# Chassis.net
KiCad netlist of a schematic drawn in Altium Designer
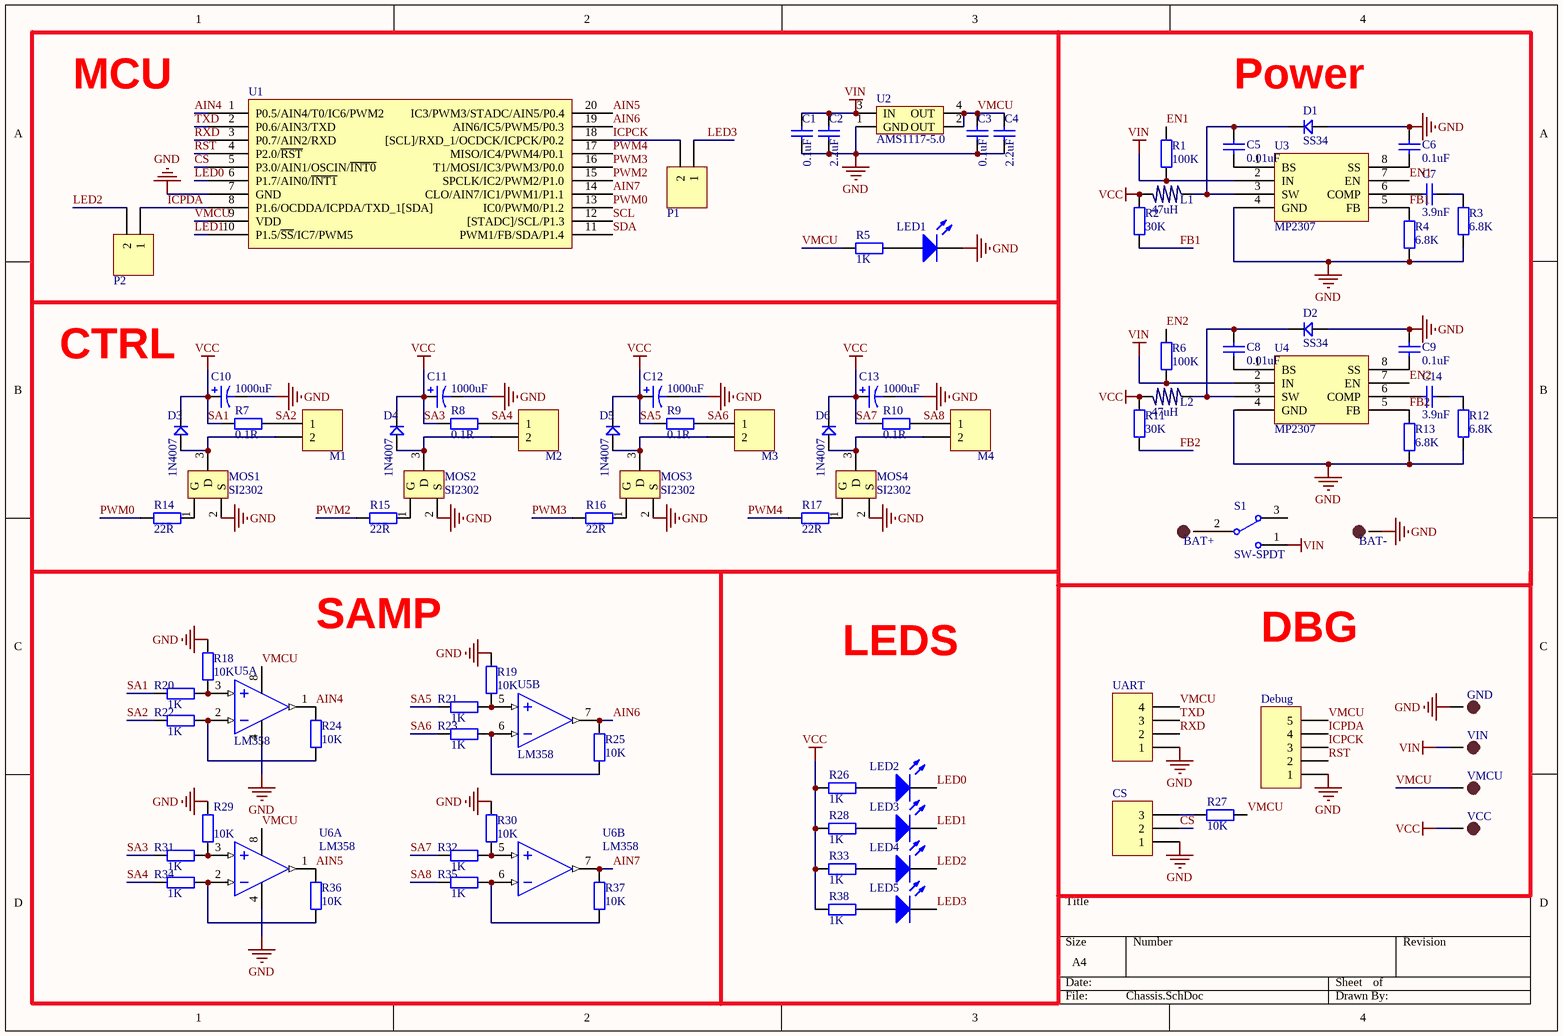
[diagram p0: Chassis.SchDoc]

(export (version "E")
  (design (tool "Eeschema 10.0.6"))
  (components
    (comp (ref "BAT+")
      (value "SPK+")
      (footprint "TP-1.5")
      (description "测试点")
      (libsource (lib "STM32F429_F746") (part "TEST-POINT"))
    )
    (comp (ref "BAT-")
      (value "SPK+")
      (footprint "TP-1.5")
      (description "测试点")
      (libsource (lib "STM32F429_F746") (part "TEST-POINT"))
    )
    (comp (ref "C1")
      (value "0.1uF")
      (footprint "0603P")
      (description "Capacitor")
      (fields (field (name "Comment") "Cap") (field (name "PUBLISHER") "Altium Limited"))
      (libsource (lib "Miscellaneous Devices") (part "Cap"))
    )
    (comp (ref "C2")
      (value "2.2uF")
      (footprint "0603P")
      (description "Capacitor")
      (fields (field (name "Comment") "Cap") (field (name "PUBLISHER") "Altium Limited"))
      (libsource (lib "Miscellaneous Devices") (part "Cap"))
    )
    (comp (ref "C3")
      (value "0.1uF")
      (footprint "0603P")
      (description "Capacitor")
      (fields (field (name "Comment") "Cap") (field (name "PUBLISHER") "Altium Limited"))
      (libsource (lib "Miscellaneous Devices") (part "Cap"))
    )
    (comp (ref "C4")
      (value "2.2uF")
      (footprint "0603P")
      (description "Capacitor")
      (fields (field (name "Comment") "Cap") (field (name "PUBLISHER") "Altium Limited"))
      (libsource (lib "Miscellaneous Devices") (part "Cap"))
    )
    (comp (ref "C5")
      (value "0.01uF")
      (footprint "0603P")
      (description "Capacitor")
      (fields (field (name "Comment") "Cap") (field (name "PUBLISHER") "Altium Limited"))
      (libsource (lib "Miscellaneous Devices") (part "Cap"))
    )
    (comp (ref "C6")
      (value "0.1uF")
      (footprint "0603P")
      (description "Capacitor")
      (fields (field (name "Comment") "Cap") (field (name "PUBLISHER") "Altium Limited"))
      (libsource (lib "Miscellaneous Devices") (part "Cap"))
    )
    (comp (ref "C7")
      (value "3.9nF")
      (footprint "0603P")
      (description "Capacitor")
      (fields (field (name "Comment") "Cap") (field (name "PUBLISHER") "Altium Limited"))
      (libsource (lib "Miscellaneous Devices") (part "Cap"))
    )
    (comp (ref "C8")
      (value "0.01uF")
      (footprint "0603P")
      (description "Capacitor")
      (fields (field (name "Comment") "Cap") (field (name "PUBLISHER") "Altium Limited"))
      (libsource (lib "Miscellaneous Devices") (part "Cap"))
    )
    (comp (ref "C9")
      (value "0.1uF")
      (footprint "0603P")
      (description "Capacitor")
      (fields (field (name "Comment") "Cap") (field (name "PUBLISHER") "Altium Limited"))
      (libsource (lib "Miscellaneous Devices") (part "Cap"))
    )
    (comp (ref "C10")
      (value "1000uF")
      (footprint "C-RB-5.0/13")
      (description "Polarized Capacitor (Radial)")
      (fields (field (name "Comment") "Cap Pol1") (field (name "PUBLISHER") "Altium Limited"))
      (libsource (lib "Miscellaneous Devices") (part "Cap Pol1"))
    )
    (comp (ref "C11")
      (value "1000uF")
      (footprint "C-RB-5.0/13")
      (description "Polarized Capacitor (Radial)")
      (fields (field (name "Comment") "Cap Pol1") (field (name "PUBLISHER") "Altium Limited"))
      (libsource (lib "Miscellaneous Devices") (part "Cap Pol1"))
    )
    (comp (ref "C12")
      (value "1000uF")
      (footprint "C-RB-5.0/13")
      (description "Polarized Capacitor (Radial)")
      (fields (field (name "Comment") "Cap Pol1") (field (name "PUBLISHER") "Altium Limited"))
      (libsource (lib "Miscellaneous Devices") (part "Cap Pol1"))
    )
    (comp (ref "C13")
      (value "1000uF")
      (footprint "C-RB-5.0/13")
      (description "Polarized Capacitor (Radial)")
      (fields (field (name "Comment") "Cap Pol1") (field (name "PUBLISHER") "Altium Limited"))
      (libsource (lib "Miscellaneous Devices") (part "Cap Pol1"))
    )
    (comp (ref "C14")
      (value "3.9nF")
      (footprint "0603P")
      (description "Capacitor")
      (fields (field (name "Comment") "Cap") (field (name "PUBLISHER") "Altium Limited"))
      (libsource (lib "Miscellaneous Devices") (part "Cap"))
    )
    (comp (ref "CS")
      (value "Header 3")
      (footprint "HDR1X3")
      (description "Header, 3-Pin")
      (fields (field (name "PUBLISHER") "Altium Limited"))
      (libsource (lib "Miscellaneous Connectors") (part "Header 3"))
    )
    (comp (ref "D1") (value "SS34") (footprint "SOD-123") (libsource (lib "STM32F429_F746") (part "D")))
    (comp (ref "D2") (value "SS34") (footprint "SOD-123") (libsource (lib "STM32F429_F746") (part "D")))
    (comp (ref "D3") (value "1N4007") (footprint "SOD-123") (libsource (lib "STM32F429_F746") (part "D")))
    (comp (ref "D4") (value "1N4007") (footprint "SOD-123") (libsource (lib "STM32F429_F746") (part "D")))
    (comp (ref "D5") (value "1N4007") (footprint "SOD-123") (libsource (lib "STM32F429_F746") (part "D")))
    (comp (ref "D6") (value "1N4007") (footprint "SOD-123") (libsource (lib "STM32F429_F746") (part "D")))
    (comp (ref "Debug")
      (value "Header 5")
      (footprint "HDR1X5")
      (description "Header, 5-Pin")
      (fields (field (name "PUBLISHER") "Altium Limited"))
      (libsource (lib "Miscellaneous Connectors") (part "Header 5"))
    )
    (comp (ref "GND")
      (value "SPK+")
      (footprint "TP-1.5")
      (description "测试点")
      (libsource (lib "STM32F429_F746") (part "TEST-POINT"))
    )
    (comp (ref "L1") (value "47uH") (footprint "0603P") (libsource (lib "STM32F429_F746") (part "L")))
    (comp (ref "L2") (value "47uH") (footprint "0603P") (libsource (lib "STM32F429_F746") (part "L")))
    (comp (ref "LED1")
      (value "LED1")
      (footprint "LED-1206")
      (description "Typical RED, GREEN, YELLOW, AMBER GaAs LED")
      (fields (field (name "PUBLISHER") "Altium Limited"))
      (libsource (lib "STM32F429_F746") (part "LED2"))
    )
    (comp (ref "LED2")
      (value "LED1")
      (footprint "LED-1206")
      (description "Typical RED, GREEN, YELLOW, AMBER GaAs LED")
      (fields (field (name "PUBLISHER") "Altium Limited"))
      (libsource (lib "STM32F429_F746") (part "LED2"))
    )
    (comp (ref "LED3")
      (value "LED1")
      (footprint "LED-1206")
      (description "Typical RED, GREEN, YELLOW, AMBER GaAs LED")
      (fields (field (name "PUBLISHER") "Altium Limited"))
      (libsource (lib "STM32F429_F746") (part "LED2"))
    )
    (comp (ref "LED4")
      (value "LED1")
      (footprint "LED-1206")
      (description "Typical RED, GREEN, YELLOW, AMBER GaAs LED")
      (fields (field (name "PUBLISHER") "Altium Limited"))
      (libsource (lib "STM32F429_F746") (part "LED2"))
    )
    (comp (ref "LED5")
      (value "LED1")
      (footprint "LED-1206")
      (description "Typical RED, GREEN, YELLOW, AMBER GaAs LED")
      (fields (field (name "PUBLISHER") "Altium Limited"))
      (libsource (lib "STM32F429_F746") (part "LED2"))
    )
    (comp (ref "M1")
      (value "Header 2")
      (footprint "HDR1X2")
      (description "Header, 2-Pin")
      (fields (field (name "PUBLISHER") "Altium Limited"))
      (libsource (lib "") (part "Header 2_1"))
    )
    (comp (ref "M2")
      (value "Header 2")
      (footprint "HDR1X2")
      (description "Header, 2-Pin")
      (fields (field (name "PUBLISHER") "Altium Limited"))
      (libsource (lib "") (part "Header 2_1"))
    )
    (comp (ref "M3")
      (value "Header 2")
      (footprint "HDR1X2")
      (description "Header, 2-Pin")
      (fields (field (name "PUBLISHER") "Altium Limited"))
      (libsource (lib "") (part "Header 2_1"))
    )
    (comp (ref "M4")
      (value "Header 2")
      (footprint "HDR1X2")
      (description "Header, 2-Pin")
      (fields (field (name "PUBLISHER") "Altium Limited"))
      (libsource (lib "") (part "Header 2_1"))
    )
    (comp (ref "MOS1")
      (value "SI2302")
      (footprint "SO-G3/C2.5")
      (description "IRLML6401/SI2301")
      (libsource (lib "STM32F429_CORE") (part "MOS-P"))
    )
    (comp (ref "MOS2")
      (value "SI2302")
      (footprint "SO-G3/C2.5")
      (description "IRLML6401/SI2301")
      (libsource (lib "STM32F429_CORE") (part "MOS-P"))
    )
    (comp (ref "MOS3")
      (value "SI2302")
      (footprint "SO-G3/C2.5")
      (description "IRLML6401/SI2301")
      (libsource (lib "STM32F429_CORE") (part "MOS-P"))
    )
    (comp (ref "MOS4")
      (value "SI2302")
      (footprint "SO-G3/C2.5")
      (description "IRLML6401/SI2301")
      (libsource (lib "STM32F429_CORE") (part "MOS-P"))
    )
    (comp (ref "P1")
      (value "Header 2")
      (footprint "HDR1X2")
      (description "Header, 2-Pin")
      (fields (field (name "PUBLISHER") "Altium Limited"))
      (libsource (lib "Miscellaneous Connectors") (part "Header 2"))
    )
    (comp (ref "P2")
      (value "Header 2")
      (footprint "HDR1X2")
      (description "Header, 2-Pin")
      (fields (field (name "PUBLISHER") "Altium Limited"))
      (libsource (lib "Miscellaneous Connectors") (part "Header 2"))
    )
    (comp (ref "R1")
      (value "100K")
      (footprint "0603P")
      (description "Resistor")
      (fields (field (name "Comment") "Res2") (field (name "PUBLISHER") "Altium Limited"))
      (libsource (lib "") (part "Res2_1"))
    )
    (comp (ref "R2")
      (value "30K")
      (footprint "0603P")
      (description "Resistor")
      (fields (field (name "Comment") "Res2") (field (name "PUBLISHER") "Altium Limited"))
      (libsource (lib "") (part "Res2_1"))
    )
    (comp (ref "R3")
      (value "6.8K")
      (footprint "0603P")
      (description "Resistor")
      (fields (field (name "Comment") "Res2") (field (name "PUBLISHER") "Altium Limited"))
      (libsource (lib "") (part "Res2_1"))
    )
    (comp (ref "R4")
      (value "6.8K")
      (footprint "0603P")
      (description "Resistor")
      (fields (field (name "Comment") "Res2") (field (name "PUBLISHER") "Altium Limited"))
      (libsource (lib "") (part "Res2_1"))
    )
    (comp (ref "R5")
      (value "1K")
      (footprint "0603P")
      (description "Resistor")
      (fields (field (name "Comment") "Res2") (field (name "PUBLISHER") "Altium Limited"))
      (libsource (lib "Miscellaneous Devices") (part "Res2"))
    )
    (comp (ref "R6")
      (value "100K")
      (footprint "0603P")
      (description "Resistor")
      (fields (field (name "Comment") "Res2") (field (name "PUBLISHER") "Altium Limited"))
      (libsource (lib "") (part "Res2_1"))
    )
    (comp (ref "R7")
      (value "0.1R")
      (footprint "2512")
      (description "Resistor")
      (fields (field (name "Comment") "Res2") (field (name "PUBLISHER") "Altium Limited"))
      (libsource (lib "Miscellaneous Devices") (part "Res2"))
    )
    (comp (ref "R8")
      (value "0.1R")
      (footprint "2512")
      (description "Resistor")
      (fields (field (name "Comment") "Res2") (field (name "PUBLISHER") "Altium Limited"))
      (libsource (lib "Miscellaneous Devices") (part "Res2"))
    )
    (comp (ref "R9")
      (value "0.1R")
      (footprint "2512")
      (description "Resistor")
      (fields (field (name "Comment") "Res2") (field (name "PUBLISHER") "Altium Limited"))
      (libsource (lib "Miscellaneous Devices") (part "Res2"))
    )
    (comp (ref "R10")
      (value "0.1R")
      (footprint "2512")
      (description "Resistor")
      (fields (field (name "Comment") "Res2") (field (name "PUBLISHER") "Altium Limited"))
      (libsource (lib "Miscellaneous Devices") (part "Res2"))
    )
    (comp (ref "R11")
      (value "30K")
      (footprint "0603p")
      (description "Resistor")
      (fields (field (name "Comment") "Res2") (field (name "PUBLISHER") "Altium Limited"))
      (libsource (lib "") (part "Res2_1"))
    )
    (comp (ref "R12")
      (value "6.8K")
      (footprint "0603p")
      (description "Resistor")
      (fields (field (name "Comment") "Res2") (field (name "PUBLISHER") "Altium Limited"))
      (libsource (lib "") (part "Res2_1"))
    )
    (comp (ref "R13")
      (value "6.8K")
      (footprint "0603p")
      (description "Resistor")
      (fields (field (name "Comment") "Res2") (field (name "PUBLISHER") "Altium Limited"))
      (libsource (lib "") (part "Res2_1"))
    )
    (comp (ref "R14")
      (value "22R")
      (footprint "0603p")
      (description "Resistor")
      (fields (field (name "Comment") "Res2") (field (name "PUBLISHER") "Altium Limited"))
      (libsource (lib "Miscellaneous Devices") (part "Res2"))
    )
    (comp (ref "R15")
      (value "22R")
      (footprint "0603p")
      (description "Resistor")
      (fields (field (name "Comment") "Res2") (field (name "PUBLISHER") "Altium Limited"))
      (libsource (lib "Miscellaneous Devices") (part "Res2"))
    )
    (comp (ref "R16")
      (value "22R")
      (footprint "0603p")
      (description "Resistor")
      (fields (field (name "Comment") "Res2") (field (name "PUBLISHER") "Altium Limited"))
      (libsource (lib "Miscellaneous Devices") (part "Res2"))
    )
    (comp (ref "R17")
      (value "22R")
      (footprint "0603p")
      (description "Resistor")
      (fields (field (name "Comment") "Res2") (field (name "PUBLISHER") "Altium Limited"))
      (libsource (lib "Miscellaneous Devices") (part "Res2"))
    )
    (comp (ref "R18")
      (value "10K")
      (footprint "0603p")
      (description "Resistor")
      (fields (field (name "Comment") "Res2") (field (name "PUBLISHER") "Altium Limited"))
      (libsource (lib "") (part "Res2_1"))
    )
    (comp (ref "R19")
      (value "10K")
      (footprint "0603p")
      (description "Resistor")
      (fields (field (name "Comment") "Res2") (field (name "PUBLISHER") "Altium Limited"))
      (libsource (lib "") (part "Res2_1"))
    )
    (comp (ref "R20")
      (value "1K")
      (footprint "0603p")
      (description "Resistor")
      (fields (field (name "Comment") "Res2") (field (name "PUBLISHER") "Altium Limited"))
      (libsource (lib "Miscellaneous Devices") (part "Res2"))
    )
    (comp (ref "R21")
      (value "1K")
      (footprint "0603p")
      (description "Resistor")
      (fields (field (name "Comment") "Res2") (field (name "PUBLISHER") "Altium Limited"))
      (libsource (lib "Miscellaneous Devices") (part "Res2"))
    )
    (comp (ref "R22")
      (value "1K")
      (footprint "0603p")
      (description "Resistor")
      (fields (field (name "Comment") "Res2") (field (name "PUBLISHER") "Altium Limited"))
      (libsource (lib "Miscellaneous Devices") (part "Res2"))
    )
    (comp (ref "R23")
      (value "1K")
      (footprint "0603p")
      (description "Resistor")
      (fields (field (name "Comment") "Res2") (field (name "PUBLISHER") "Altium Limited"))
      (libsource (lib "Miscellaneous Devices") (part "Res2"))
    )
    (comp (ref "R24")
      (value "10K")
      (footprint "0603p")
      (description "Resistor")
      (fields (field (name "Comment") "Res2") (field (name "PUBLISHER") "Altium Limited"))
      (libsource (lib "") (part "Res2_1"))
    )
    (comp (ref "R25")
      (value "10K")
      (footprint "0603p")
      (description "Resistor")
      (fields (field (name "Comment") "Res2") (field (name "PUBLISHER") "Altium Limited"))
      (libsource (lib "") (part "Res2_1"))
    )
    (comp (ref "R26")
      (value "1K")
      (footprint "0603p")
      (description "Resistor")
      (fields (field (name "Comment") "Res2") (field (name "PUBLISHER") "Altium Limited"))
      (libsource (lib "Miscellaneous Devices") (part "Res2"))
    )
    (comp (ref "R27")
      (value "10K")
      (footprint "0603p")
      (description "Resistor")
      (fields (field (name "Comment") "Res2") (field (name "PUBLISHER") "Altium Limited"))
      (libsource (lib "Miscellaneous Devices") (part "Res2"))
    )
    (comp (ref "R28")
      (value "1K")
      (footprint "0603p")
      (description "Resistor")
      (fields (field (name "Comment") "Res2") (field (name "PUBLISHER") "Altium Limited"))
      (libsource (lib "Miscellaneous Devices") (part "Res2"))
    )
    (comp (ref "R29")
      (value "10K")
      (footprint "0603p")
      (description "Resistor")
      (fields (field (name "Comment") "Res2") (field (name "PUBLISHER") "Altium Limited"))
      (libsource (lib "") (part "Res2_1"))
    )
    (comp (ref "R30")
      (value "10K")
      (footprint "0603p")
      (description "Resistor")
      (fields (field (name "Comment") "Res2") (field (name "PUBLISHER") "Altium Limited"))
      (libsource (lib "") (part "Res2_1"))
    )
    (comp (ref "R31")
      (value "1K")
      (footprint "0603p")
      (description "Resistor")
      (fields (field (name "Comment") "Res2") (field (name "PUBLISHER") "Altium Limited"))
      (libsource (lib "Miscellaneous Devices") (part "Res2"))
    )
    (comp (ref "R32")
      (value "1K")
      (footprint "0603p")
      (description "Resistor")
      (fields (field (name "Comment") "Res2") (field (name "PUBLISHER") "Altium Limited"))
      (libsource (lib "Miscellaneous Devices") (part "Res2"))
    )
    (comp (ref "R33")
      (value "1K")
      (footprint "0603p")
      (description "Resistor")
      (fields (field (name "Comment") "Res2") (field (name "PUBLISHER") "Altium Limited"))
      (libsource (lib "Miscellaneous Devices") (part "Res2"))
    )
    (comp (ref "R34")
      (value "1K")
      (footprint "0603p")
      (description "Resistor")
      (fields (field (name "Comment") "Res2") (field (name "PUBLISHER") "Altium Limited"))
      (libsource (lib "Miscellaneous Devices") (part "Res2"))
    )
    (comp (ref "R35")
      (value "1K")
      (footprint "0603p")
      (description "Resistor")
      (fields (field (name "Comment") "Res2") (field (name "PUBLISHER") "Altium Limited"))
      (libsource (lib "Miscellaneous Devices") (part "Res2"))
    )
    (comp (ref "R36")
      (value "10K")
      (footprint "0603p")
      (description "Resistor")
      (fields (field (name "Comment") "Res2") (field (name "PUBLISHER") "Altium Limited"))
      (libsource (lib "") (part "Res2_1"))
    )
    (comp (ref "R37")
      (value "10K")
      (footprint "0603p")
      (description "Resistor")
      (fields (field (name "Comment") "Res2") (field (name "PUBLISHER") "Altium Limited"))
      (libsource (lib "") (part "Res2_1"))
    )
    (comp (ref "R38")
      (value "1K")
      (footprint "0603p")
      (description "Resistor")
      (fields (field (name "Comment") "Res2") (field (name "PUBLISHER") "Altium Limited"))
      (libsource (lib "Miscellaneous Devices") (part "Res2"))
    )
    (comp (ref "S1")
      (value "SW-SPDT")
      (footprint "SWITCH_A3")
      (description "开关")
      (fields (field (name "PUBLISHER") "Altium Limited"))
      (libsource (lib "fszhang") (part "SW-SPDT"))
    )
    (comp (ref "U1")
      (value "N76E003")
      (footprint "SSOP-20_208mil")
      (libsource (lib "nvton") (part "N76E003"))
    )
    (comp (ref "U2")
      (value "AMS1117-5.0")
      (footprint "AMS1117")
      (libsource (lib "STM32F429_F746") (part "AMS1117"))
    )
    (comp (ref "U3") (value "MP2307") (footprint "SOP-8") (libsource (lib "STM32F429_F746") (part "MP2307")))
    (comp (ref "U4") (value "MP2307") (footprint "SOP-8") (libsource (lib "STM32F429_F746") (part "MP2307")))
    (comp (ref "U5")
      (value "LM358")
      (footprint "SOIC-8")
      (description "双运放")
      (libsource (lib "fszhang") (part "LM358"))
    )
    (comp (ref "U6")
      (value "LM358")
      (footprint "SOIC-8")
      (description "双运放")
      (libsource (lib "fszhang") (part "LM358"))
    )
    (comp (ref "UART")
      (value "Header 4")
      (footprint "HDR1X4")
      (description "Header, 4-Pin")
      (fields (field (name "PUBLISHER") "Altium Limited"))
      (libsource (lib "Miscellaneous Connectors") (part "Header 4"))
    )
    (comp (ref "VCC")
      (value "SPK+")
      (footprint "TP-1.5")
      (description "测试点")
      (libsource (lib "STM32F429_F746") (part "TEST-POINT"))
    )
    (comp (ref "VIN")
      (value "SPK+")
      (footprint "TP-1.5")
      (description "测试点")
      (libsource (lib "STM32F429_F746") (part "TEST-POINT"))
    )
    (comp (ref "VMCU")
      (value "SPK+")
      (footprint "TP-1.5")
      (description "测试点")
      (libsource (lib "STM32F429_F746") (part "TEST-POINT"))
    )
  )
  (nets
    (net (code "1") (name "/AIN4") (class "Default")
      (node (ref "R24") (pin "2") (pinfunction "2_2") (pintype "passive"))
      (node (ref "U1") (pin "1") (pinfunction "P0.5/AIN4/T0/IC6/PWM2_1") (pintype "passive"))
      (node (ref "U5") (pin "1") (pinfunction "OUT_1") (pintype "output"))
    )
    (net (code "2") (name "/AIN5") (class "Default")
      (node (ref "R36") (pin "2") (pinfunction "2_2") (pintype "passive"))
      (node (ref "U1") (pin "20") (pinfunction "IC3/PWM3/STADC/AIN5/P0.4_20") (pintype "passive"))
      (node (ref "U6") (pin "1") (pinfunction "OUT_1") (pintype "output"))
    )
    (net (code "3") (name "/AIN6") (class "Default")
      (node (ref "R25") (pin "2") (pinfunction "2_2") (pintype "passive"))
      (node (ref "U1") (pin "19") (pinfunction "AIN6/IC5/PWM5/P0.3_19") (pintype "passive"))
      (node (ref "U5") (pin "7") (pinfunction "OUT_7") (pintype "output"))
    )
    (net (code "4") (name "/AIN7") (class "Default")
      (node (ref "R37") (pin "2") (pinfunction "2_2") (pintype "passive"))
      (node (ref "U1") (pin "14") (pinfunction "CLO/AIN7/IC1/PWM1/P1.1_14") (pintype "passive"))
      (node (ref "U6") (pin "7") (pinfunction "OUT_7") (pintype "output"))
    )
    (net (code "5") (name "/CS") (class "Default")
      (node (ref "CS") (pin "2") (pinfunction "2_2") (pintype "passive"))
      (node (ref "U1") (pin "5") (pinfunction "P3.0/AIN1/OSCIN/~{INT0}_5") (pintype "passive"))
    )
    (net (code "6") (name "/EN1") (class "Default")
      (node (ref "R1") (pin "2") (pinfunction "2_2") (pintype "passive"))
      (node (ref "U3") (pin "7") (pinfunction "EN_7") (pintype "passive"))
    )
    (net (code "7") (name "/EN2") (class "Default")
      (node (ref "R6") (pin "2") (pinfunction "2_2") (pintype "passive"))
      (node (ref "U4") (pin "7") (pinfunction "EN_7") (pintype "passive"))
    )
    (net (code "8") (name "/FB1") (class "Default")
      (node (ref "R2") (pin "1") (pinfunction "1_1") (pintype "passive"))
      (node (ref "R4") (pin "2") (pinfunction "2_2") (pintype "passive"))
      (node (ref "U3") (pin "5") (pinfunction "FB_5") (pintype "passive"))
    )
    (net (code "9") (name "/FB2") (class "Default")
      (node (ref "R11") (pin "1") (pinfunction "1_1") (pintype "passive"))
      (node (ref "R13") (pin "2") (pinfunction "2_2") (pintype "passive"))
      (node (ref "U4") (pin "5") (pinfunction "FB_5") (pintype "passive"))
    )
    (net (code "10") (name "/ICPCK") (class "Default")
      (node (ref "Debug") (pin "3") (pinfunction "3_3") (pintype "passive"))
      (node (ref "P1") (pin "2") (pinfunction "2_2") (pintype "passive"))
      (node (ref "U1") (pin "18") (pinfunction "[SCL]/RXD_1/OCDCK/ICPCK/P0.2_18") (pintype "passive"))
    )
    (net (code "11") (name "/ICPDA") (class "Default")
      (node (ref "Debug") (pin "4") (pinfunction "4_4") (pintype "passive"))
      (node (ref "P2") (pin "1") (pinfunction "1_1") (pintype "passive"))
      (node (ref "U1") (pin "8") (pinfunction "P1.6/OCDDA/ICPDA/TXD_1[SDA]_8") (pintype "passive"))
    )
    (net (code "12") (name "/LED0") (class "Default")
      (node (ref "LED2") (pin "2") (pinfunction "K_2") (pintype "passive"))
      (node (ref "U1") (pin "6") (pinfunction "P1.7/AIN0/~{INT1}_6") (pintype "passive"))
    )
    (net (code "13") (name "/LED1") (class "Default")
      (node (ref "LED3") (pin "2") (pinfunction "K_2") (pintype "passive"))
      (node (ref "U1") (pin "10") (pinfunction "P1.5/~{SS}/IC7/PWM5_10") (pintype "passive"))
    )
    (net (code "14") (name "/LED2") (class "Default")
      (node (ref "LED4") (pin "2") (pinfunction "K_2") (pintype "passive"))
      (node (ref "P2") (pin "2") (pinfunction "2_2") (pintype "passive"))
    )
    (net (code "15") (name "/LED3") (class "Default")
      (node (ref "LED5") (pin "2") (pinfunction "K_2") (pintype "passive"))
      (node (ref "P1") (pin "1") (pinfunction "1_1") (pintype "passive"))
    )
    (net (code "16") (name "/PWM0") (class "Default")
      (node (ref "R14") (pin "1") (pinfunction "1_1") (pintype "passive"))
      (node (ref "U1") (pin "13") (pinfunction "IC0/PWM0/P1.2_13") (pintype "passive"))
    )
    (net (code "17") (name "/PWM2") (class "Default")
      (node (ref "R15") (pin "1") (pinfunction "1_1") (pintype "passive"))
      (node (ref "U1") (pin "15") (pinfunction "SPCLK/IC2/PWM2/P1.0_15") (pintype "passive"))
    )
    (net (code "18") (name "/PWM3") (class "Default")
      (node (ref "R16") (pin "1") (pinfunction "1_1") (pintype "passive"))
      (node (ref "U1") (pin "16") (pinfunction "T1/MOSI/IC3/PWM3/P0.0_16") (pintype "passive"))
    )
    (net (code "19") (name "/PWM4") (class "Default")
      (node (ref "R17") (pin "1") (pinfunction "1_1") (pintype "passive"))
      (node (ref "U1") (pin "17") (pinfunction "MISO/IC4/PWM4/P0.1_17") (pintype "passive"))
    )
    (net (code "20") (name "/RST") (class "Default")
      (node (ref "Debug") (pin "2") (pinfunction "2_2") (pintype "passive"))
      (node (ref "U1") (pin "4") (pinfunction "P2.0/~{RST}_4") (pintype "passive"))
    )
    (net (code "21") (name "/RXD") (class "Default")
      (node (ref "U1") (pin "3") (pinfunction "P0.7/AIN2/RXD_3") (pintype "passive"))
      (node (ref "UART") (pin "2") (pinfunction "2_2") (pintype "passive"))
    )
    (net (code "22") (name "/SA2") (class "Default")
      (node (ref "M1") (pin "1") (pinfunction "1_1") (pintype "passive"))
      (node (ref "R22") (pin "1") (pinfunction "1_1") (pintype "passive"))
      (node (ref "R7") (pin "2") (pinfunction "2_2") (pintype "passive"))
    )
    (net (code "23") (name "/SA4") (class "Default")
      (node (ref "M2") (pin "1") (pinfunction "1_1") (pintype "passive"))
      (node (ref "R34") (pin "1") (pinfunction "1_1") (pintype "passive"))
      (node (ref "R8") (pin "2") (pinfunction "2_2") (pintype "passive"))
    )
    (net (code "24") (name "/SA6") (class "Default")
      (node (ref "M3") (pin "1") (pinfunction "1_1") (pintype "passive"))
      (node (ref "R23") (pin "1") (pinfunction "1_1") (pintype "passive"))
      (node (ref "R9") (pin "2") (pinfunction "2_2") (pintype "passive"))
    )
    (net (code "25") (name "/SA8") (class "Default")
      (node (ref "M4") (pin "1") (pinfunction "1_1") (pintype "passive"))
      (node (ref "R10") (pin "2") (pinfunction "2_2") (pintype "passive"))
      (node (ref "R35") (pin "1") (pinfunction "1_1") (pintype "passive"))
    )
    (net (code "26") (name "/SCL") (class "Default")
      (node (ref "U1") (pin "12") (pinfunction "[STADC]/SCL/P1.3_12") (pintype "passive"))
    )
    (net (code "27") (name "/SDA") (class "Default")
      (node (ref "U1") (pin "11") (pinfunction "PWM1/FB/SDA/P1.4_11") (pintype "passive"))
    )
    (net (code "28") (name "/TXD") (class "Default")
      (node (ref "U1") (pin "2") (pinfunction "P0.6/AIN3/TXD_2") (pintype "passive"))
      (node (ref "UART") (pin "3") (pinfunction "3_3") (pintype "passive"))
    )
    (net (code "29") (name "/VMCU") (class "Default")
      (node (ref "C3") (pin "2") (pinfunction "2_2") (pintype "passive"))
      (node (ref "C4") (pin "2") (pinfunction "2_2") (pintype "passive"))
      (node (ref "Debug") (pin "5") (pinfunction "5_5") (pintype "passive"))
      (node (ref "R27") (pin "2") (pinfunction "2_2") (pintype "passive"))
      (node (ref "R5") (pin "1") (pinfunction "1_1") (pintype "passive"))
      (node (ref "U1") (pin "9") (pinfunction "VDD_9") (pintype "passive"))
      (node (ref "U2") (pin "2") (pinfunction "OUT_2") (pintype "passive"))
      (node (ref "U2") (pin "4") (pinfunction "OUT_4") (pintype "passive"))
      (node (ref "U5") (pin "8") (pinfunction "V+_8") (pintype "passive"))
      (node (ref "U6") (pin "8") (pinfunction "V+_8") (pintype "passive"))
      (node (ref "UART") (pin "4") (pinfunction "4_4") (pintype "passive"))
      (node (ref "VMCU") (pin "1") (pinfunction "1_1") (pintype "passive"))
    )
    (net (code "30") (name "GND") (class "Default")
      (node (ref "BAT-") (pin "1") (pinfunction "1_1") (pintype "passive"))
      (node (ref "C1") (pin "1") (pinfunction "1_1") (pintype "passive"))
      (node (ref "C10") (pin "2") (pinfunction "2_2") (pintype "passive"))
      (node (ref "C11") (pin "2") (pinfunction "2_2") (pintype "passive"))
      (node (ref "C12") (pin "2") (pinfunction "2_2") (pintype "passive"))
      (node (ref "C13") (pin "2") (pinfunction "2_2") (pintype "passive"))
      (node (ref "C2") (pin "1") (pinfunction "1_1") (pintype "passive"))
      (node (ref "C3") (pin "1") (pinfunction "1_1") (pintype "passive"))
      (node (ref "C4") (pin "1") (pinfunction "1_1") (pintype "passive"))
      (node (ref "C6") (pin "2") (pinfunction "2_2") (pintype "passive"))
      (node (ref "C9") (pin "2") (pinfunction "2_2") (pintype "passive"))
      (node (ref "CS") (pin "1") (pinfunction "1_1") (pintype "passive"))
      (node (ref "D1") (pin "1") (pintype "passive"))
      (node (ref "D2") (pin "1") (pintype "passive"))
      (node (ref "Debug") (pin "1") (pinfunction "1_1") (pintype "passive"))
      (node (ref "GND") (pin "1") (pinfunction "1_1") (pintype "passive"))
      (node (ref "LED1") (pin "2") (pinfunction "K_2") (pintype "passive"))
      (node (ref "MOS1") (pin "2") (pinfunction "S_2") (pintype "passive"))
      (node (ref "MOS2") (pin "2") (pinfunction "S_2") (pintype "passive"))
      (node (ref "MOS3") (pin "2") (pinfunction "S_2") (pintype "passive"))
      (node (ref "MOS4") (pin "2") (pinfunction "S_2") (pintype "passive"))
      (node (ref "R12") (pin "1") (pinfunction "1_1") (pintype "passive"))
      (node (ref "R13") (pin "1") (pinfunction "1_1") (pintype "passive"))
      (node (ref "R18") (pin "2") (pinfunction "2_2") (pintype "passive"))
      (node (ref "R19") (pin "2") (pinfunction "2_2") (pintype "passive"))
      (node (ref "R29") (pin "2") (pinfunction "2_2") (pintype "passive"))
      (node (ref "R3") (pin "1") (pinfunction "1_1") (pintype "passive"))
      (node (ref "R30") (pin "2") (pinfunction "2_2") (pintype "passive"))
      (node (ref "R4") (pin "1") (pinfunction "1_1") (pintype "passive"))
      (node (ref "U1") (pin "7") (pinfunction "GND_7") (pintype "passive"))
      (node (ref "U2") (pin "1") (pinfunction "GND_1") (pintype "passive"))
      (node (ref "U3") (pin "4") (pinfunction "GND_4") (pintype "passive"))
      (node (ref "U4") (pin "4") (pinfunction "GND_4") (pintype "passive"))
      (node (ref "U5") (pin "4") (pinfunction "V-_4") (pintype "passive"))
      (node (ref "U6") (pin "4") (pinfunction "V-_4") (pintype "passive"))
      (node (ref "UART") (pin "1") (pinfunction "1_1") (pintype "passive"))
    )
    (net (code "31") (name "Net-(BAT+-Pad1)") (class "Default")
      (node (ref "BAT+") (pin "1") (pinfunction "1_1") (pintype "passive"))
      (node (ref "S1") (pin "2") (pinfunction "2_2") (pintype "passive"))
    )
    (net (code "32") (name "Net-(C7-Pad1)") (class "Default")
      (node (ref "C7") (pin "1") (pinfunction "1_1") (pintype "passive"))
      (node (ref "R3") (pin "2") (pinfunction "2_2") (pintype "passive"))
    )
    (net (code "33") (name "Net-(C14-Pad1)") (class "Default")
      (node (ref "C14") (pin "1") (pinfunction "1_1") (pintype "passive"))
      (node (ref "R12") (pin "2") (pinfunction "2_2") (pintype "passive"))
    )
    (net (code "34") (name "Net-(CS-Pad3)") (class "Default")
      (node (ref "CS") (pin "3") (pinfunction "3_3") (pintype "passive"))
      (node (ref "R27") (pin "1") (pinfunction "1_1") (pintype "passive"))
    )
    (net (code "35") (name "Net-(LED1-A)") (class "Default")
      (node (ref "LED1") (pin "1") (pinfunction "A_1") (pintype "passive"))
      (node (ref "R5") (pin "2") (pinfunction "2_2") (pintype "passive"))
    )
    (net (code "36") (name "Net-(LED2-A)") (class "Default")
      (node (ref "LED2") (pin "1") (pinfunction "A_1") (pintype "passive"))
      (node (ref "R26") (pin "2") (pinfunction "2_2") (pintype "passive"))
    )
    (net (code "37") (name "Net-(LED3-A)") (class "Default")
      (node (ref "LED3") (pin "1") (pinfunction "A_1") (pintype "passive"))
      (node (ref "R28") (pin "2") (pinfunction "2_2") (pintype "passive"))
    )
    (net (code "38") (name "Net-(LED4-A)") (class "Default")
      (node (ref "LED4") (pin "1") (pinfunction "A_1") (pintype "passive"))
      (node (ref "R33") (pin "2") (pinfunction "2_2") (pintype "passive"))
    )
    (net (code "39") (name "Net-(LED5-A)") (class "Default")
      (node (ref "LED5") (pin "1") (pinfunction "A_1") (pintype "passive"))
      (node (ref "R38") (pin "2") (pinfunction "2_2") (pintype "passive"))
    )
    (net (code "40") (name "Net-(MOS1-D)") (class "Default")
      (node (ref "D3") (pin "1") (pintype "passive"))
      (node (ref "M1") (pin "2") (pinfunction "2_2") (pintype "passive"))
      (node (ref "MOS1") (pin "3") (pinfunction "D_3") (pintype "passive"))
    )
    (net (code "41") (name "Net-(MOS1-G)") (class "Default")
      (node (ref "MOS1") (pin "1") (pinfunction "G_1") (pintype "passive"))
      (node (ref "R14") (pin "2") (pinfunction "2_2") (pintype "passive"))
    )
    (net (code "42") (name "Net-(MOS2-D)") (class "Default")
      (node (ref "D4") (pin "1") (pintype "passive"))
      (node (ref "M2") (pin "2") (pinfunction "2_2") (pintype "passive"))
      (node (ref "MOS2") (pin "3") (pinfunction "D_3") (pintype "passive"))
    )
    (net (code "43") (name "Net-(MOS2-G)") (class "Default")
      (node (ref "MOS2") (pin "1") (pinfunction "G_1") (pintype "passive"))
      (node (ref "R15") (pin "2") (pinfunction "2_2") (pintype "passive"))
    )
    (net (code "44") (name "Net-(MOS3-D)") (class "Default")
      (node (ref "D5") (pin "1") (pintype "passive"))
      (node (ref "M3") (pin "2") (pinfunction "2_2") (pintype "passive"))
      (node (ref "MOS3") (pin "3") (pinfunction "D_3") (pintype "passive"))
    )
    (net (code "45") (name "Net-(MOS3-G)") (class "Default")
      (node (ref "MOS3") (pin "1") (pinfunction "G_1") (pintype "passive"))
      (node (ref "R16") (pin "2") (pinfunction "2_2") (pintype "passive"))
    )
    (net (code "46") (name "Net-(MOS4-D)") (class "Default")
      (node (ref "D6") (pin "1") (pintype "passive"))
      (node (ref "M4") (pin "2") (pinfunction "2_2") (pintype "passive"))
      (node (ref "MOS4") (pin "3") (pinfunction "D_3") (pintype "passive"))
    )
    (net (code "47") (name "Net-(MOS4-G)") (class "Default")
      (node (ref "MOS4") (pin "1") (pinfunction "G_1") (pintype "passive"))
      (node (ref "R17") (pin "2") (pinfunction "2_2") (pintype "passive"))
    )
    (net (code "48") (name "Net-(U3-BS)") (class "Default")
      (node (ref "C5") (pin "1") (pinfunction "1_1") (pintype "passive"))
      (node (ref "U3") (pin "1") (pinfunction "BS_1") (pintype "passive"))
    )
    (net (code "49") (name "Net-(U3-COMP)") (class "Default")
      (node (ref "C7") (pin "2") (pinfunction "2_2") (pintype "passive"))
      (node (ref "U3") (pin "6") (pinfunction "COMP_6") (pintype "passive"))
    )
    (net (code "50") (name "Net-(U3-SS)") (class "Default")
      (node (ref "C6") (pin "1") (pinfunction "1_1") (pintype "passive"))
      (node (ref "U3") (pin "8") (pinfunction "SS_8") (pintype "passive"))
    )
    (net (code "51") (name "Net-(U3-SW)") (class "Default")
      (node (ref "C5") (pin "2") (pinfunction "2_2") (pintype "passive"))
      (node (ref "D1") (pin "2") (pintype "passive"))
      (node (ref "L1") (pin "1") (pintype "passive"))
      (node (ref "U3") (pin "3") (pinfunction "SW_3") (pintype "passive"))
    )
    (net (code "52") (name "Net-(U4-BS)") (class "Default")
      (node (ref "C8") (pin "1") (pinfunction "1_1") (pintype "passive"))
      (node (ref "U4") (pin "1") (pinfunction "BS_1") (pintype "passive"))
    )
    (net (code "53") (name "Net-(U4-COMP)") (class "Default")
      (node (ref "C14") (pin "2") (pinfunction "2_2") (pintype "passive"))
      (node (ref "U4") (pin "6") (pinfunction "COMP_6") (pintype "passive"))
    )
    (net (code "54") (name "Net-(U4-SS)") (class "Default")
      (node (ref "C9") (pin "1") (pinfunction "1_1") (pintype "passive"))
      (node (ref "U4") (pin "8") (pinfunction "SS_8") (pintype "passive"))
    )
    (net (code "55") (name "Net-(U4-SW)") (class "Default")
      (node (ref "C8") (pin "2") (pinfunction "2_2") (pintype "passive"))
      (node (ref "D2") (pin "2") (pintype "passive"))
      (node (ref "L2") (pin "1") (pintype "passive"))
      (node (ref "U4") (pin "3") (pinfunction "SW_3") (pintype "passive"))
    )
    (net (code "56") (name "Net-(U5A-IN+)") (class "Default")
      (node (ref "R18") (pin "1") (pinfunction "1_1") (pintype "passive"))
      (node (ref "R20") (pin "2") (pinfunction "2_2") (pintype "passive"))
      (node (ref "U5") (pin "3") (pinfunction "IN+_3") (pintype "input"))
    )
    (net (code "57") (name "Net-(U5A-IN-)") (class "Default")
      (node (ref "R22") (pin "2") (pinfunction "2_2") (pintype "passive"))
      (node (ref "R24") (pin "1") (pinfunction "1_1") (pintype "passive"))
      (node (ref "U5") (pin "2") (pinfunction "IN-_2") (pintype "input"))
    )
    (net (code "58") (name "Net-(U5B-IN+)") (class "Default")
      (node (ref "R19") (pin "1") (pinfunction "1_1") (pintype "passive"))
      (node (ref "R21") (pin "2") (pinfunction "2_2") (pintype "passive"))
      (node (ref "U5") (pin "5") (pinfunction "IN+_5") (pintype "input"))
    )
    (net (code "59") (name "Net-(U5B-IN-)") (class "Default")
      (node (ref "R23") (pin "2") (pinfunction "2_2") (pintype "passive"))
      (node (ref "R25") (pin "1") (pinfunction "1_1") (pintype "passive"))
      (node (ref "U5") (pin "6") (pinfunction "IN-_6") (pintype "input"))
    )
    (net (code "60") (name "Net-(U6A-IN+)") (class "Default")
      (node (ref "R29") (pin "1") (pinfunction "1_1") (pintype "passive"))
      (node (ref "R31") (pin "2") (pinfunction "2_2") (pintype "passive"))
      (node (ref "U6") (pin "3") (pinfunction "IN+_3") (pintype "input"))
    )
    (net (code "61") (name "Net-(U6A-IN-)") (class "Default")
      (node (ref "R34") (pin "2") (pinfunction "2_2") (pintype "passive"))
      (node (ref "R36") (pin "1") (pinfunction "1_1") (pintype "passive"))
      (node (ref "U6") (pin "2") (pinfunction "IN-_2") (pintype "input"))
    )
    (net (code "62") (name "Net-(U6B-IN+)") (class "Default")
      (node (ref "R30") (pin "1") (pinfunction "1_1") (pintype "passive"))
      (node (ref "R32") (pin "2") (pinfunction "2_2") (pintype "passive"))
      (node (ref "U6") (pin "5") (pinfunction "IN+_5") (pintype "input"))
    )
    (net (code "63") (name "Net-(U6B-IN-)") (class "Default")
      (node (ref "R35") (pin "2") (pinfunction "2_2") (pintype "passive"))
      (node (ref "R37") (pin "1") (pinfunction "1_1") (pintype "passive"))
      (node (ref "U6") (pin "6") (pinfunction "IN-_6") (pintype "input"))
    )
    (net (code "64") (name "VCC") (class "Default")
      (node (ref "C10") (pin "1") (pinfunction "1_1") (pintype "passive"))
      (node (ref "C11") (pin "1") (pinfunction "1_1") (pintype "passive"))
      (node (ref "C12") (pin "1") (pinfunction "1_1") (pintype "passive"))
      (node (ref "C13") (pin "1") (pinfunction "1_1") (pintype "passive"))
      (node (ref "D3") (pin "2") (pintype "passive"))
      (node (ref "D4") (pin "2") (pintype "passive"))
      (node (ref "D5") (pin "2") (pintype "passive"))
      (node (ref "D6") (pin "2") (pintype "passive"))
      (node (ref "L1") (pin "2") (pintype "passive"))
      (node (ref "L2") (pin "2") (pintype "passive"))
      (node (ref "R10") (pin "1") (pinfunction "1_1") (pintype "passive"))
      (node (ref "R11") (pin "2") (pinfunction "2_2") (pintype "passive"))
      (node (ref "R2") (pin "2") (pinfunction "2_2") (pintype "passive"))
      (node (ref "R20") (pin "1") (pinfunction "1_1") (pintype "passive"))
      (node (ref "R21") (pin "1") (pinfunction "1_1") (pintype "passive"))
      (node (ref "R26") (pin "1") (pinfunction "1_1") (pintype "passive"))
      (node (ref "R28") (pin "1") (pinfunction "1_1") (pintype "passive"))
      (node (ref "R31") (pin "1") (pinfunction "1_1") (pintype "passive"))
      (node (ref "R32") (pin "1") (pinfunction "1_1") (pintype "passive"))
      (node (ref "R33") (pin "1") (pinfunction "1_1") (pintype "passive"))
      (node (ref "R38") (pin "1") (pinfunction "1_1") (pintype "passive"))
      (node (ref "R7") (pin "1") (pinfunction "1_1") (pintype "passive"))
      (node (ref "R8") (pin "1") (pinfunction "1_1") (pintype "passive"))
      (node (ref "R9") (pin "1") (pinfunction "1_1") (pintype "passive"))
      (node (ref "VCC") (pin "1") (pinfunction "1_1") (pintype "passive"))
    )
    (net (code "65") (name "VIN") (class "Default")
      (node (ref "C1") (pin "2") (pinfunction "2_2") (pintype "passive"))
      (node (ref "C2") (pin "2") (pinfunction "2_2") (pintype "passive"))
      (node (ref "R1") (pin "1") (pinfunction "1_1") (pintype "passive"))
      (node (ref "R6") (pin "1") (pinfunction "1_1") (pintype "passive"))
      (node (ref "S1") (pin "1") (pinfunction "1_1") (pintype "passive"))
      (node (ref "U2") (pin "3") (pinfunction "IN_3") (pintype "passive"))
      (node (ref "U3") (pin "2") (pinfunction "IN_2") (pintype "passive"))
      (node (ref "U4") (pin "2") (pinfunction "IN_2") (pintype "passive"))
      (node (ref "VIN") (pin "1") (pinfunction "1_1") (pintype "passive"))
    )
    (net (code "66") (name "unconnected-(S1-Pad3)") (class "Default")
      (node (ref "S1") (pin "3") (pinfunction "3_3") (pintype "passive"))
    )
  )
)
